# P-MOS.net
KiCad netlist of a schematic drawn in Altium Designer
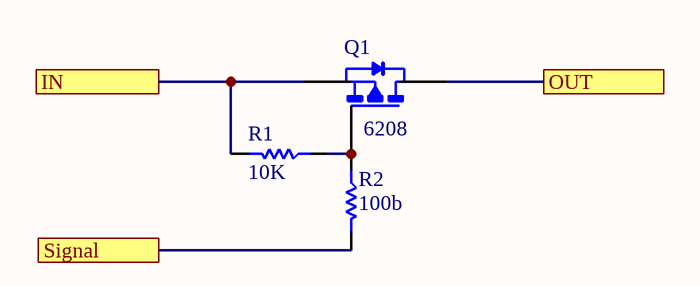
[diagram p0: P-MOS.SchDoc]

(export (version "E")
  (design (tool "Eeschema 10.0.6"))
  (components
    (comp (ref "Q1")
      (value "P-Channel")
      (footprint "SOT23_N")
      (description "P-Channel MOSFET")
      (fields (field (name "INFLOW") "6208"))
      (libsource (lib "aKaReZa") (part "Semi_MOSFET_Si2301DS"))
    )
    (comp (ref "R1")
      (value "10K")
      (footprint "RES 0805 (2012X06L)")
      (description "Resistor")
      (libsource (lib "aKaReZa") (part "Res_SMD_0805"))
    )
    (comp (ref "R2")
      (value "100b")
      (footprint "RES 0805 (2012X06L)")
      (description "Resistor")
      (libsource (lib "aKaReZa") (part "Res_SMD_0805"))
    )
  )
  (nets
    (net (code "1") (name "/IN") (class "Default")
      (node (ref "Q1") (pin "2") (pinfunction "S_2") (pintype "passive"))
      (node (ref "R1") (pin "2") (pinfunction "2_2") (pintype "passive"))
    )
    (net (code "2") (name "/OUT") (class "Default")
      (node (ref "Q1") (pin "3") (pinfunction "D_3") (pintype "passive"))
    )
    (net (code "3") (name "/Signal") (class "Default")
      (node (ref "R2") (pin "2") (pinfunction "2_2") (pintype "passive"))
    )
    (net (code "4") (name "Net-(Q1-G)") (class "Default")
      (node (ref "Q1") (pin "1") (pinfunction "G_1") (pintype "passive"))
      (node (ref "R1") (pin "1") (pinfunction "1_1") (pintype "passive"))
      (node (ref "R2") (pin "1") (pinfunction "1_1") (pintype "passive"))
    )
  )
)
